# AudioMega_v1.net
KiCad netlist of a schematic drawn in EAGLE
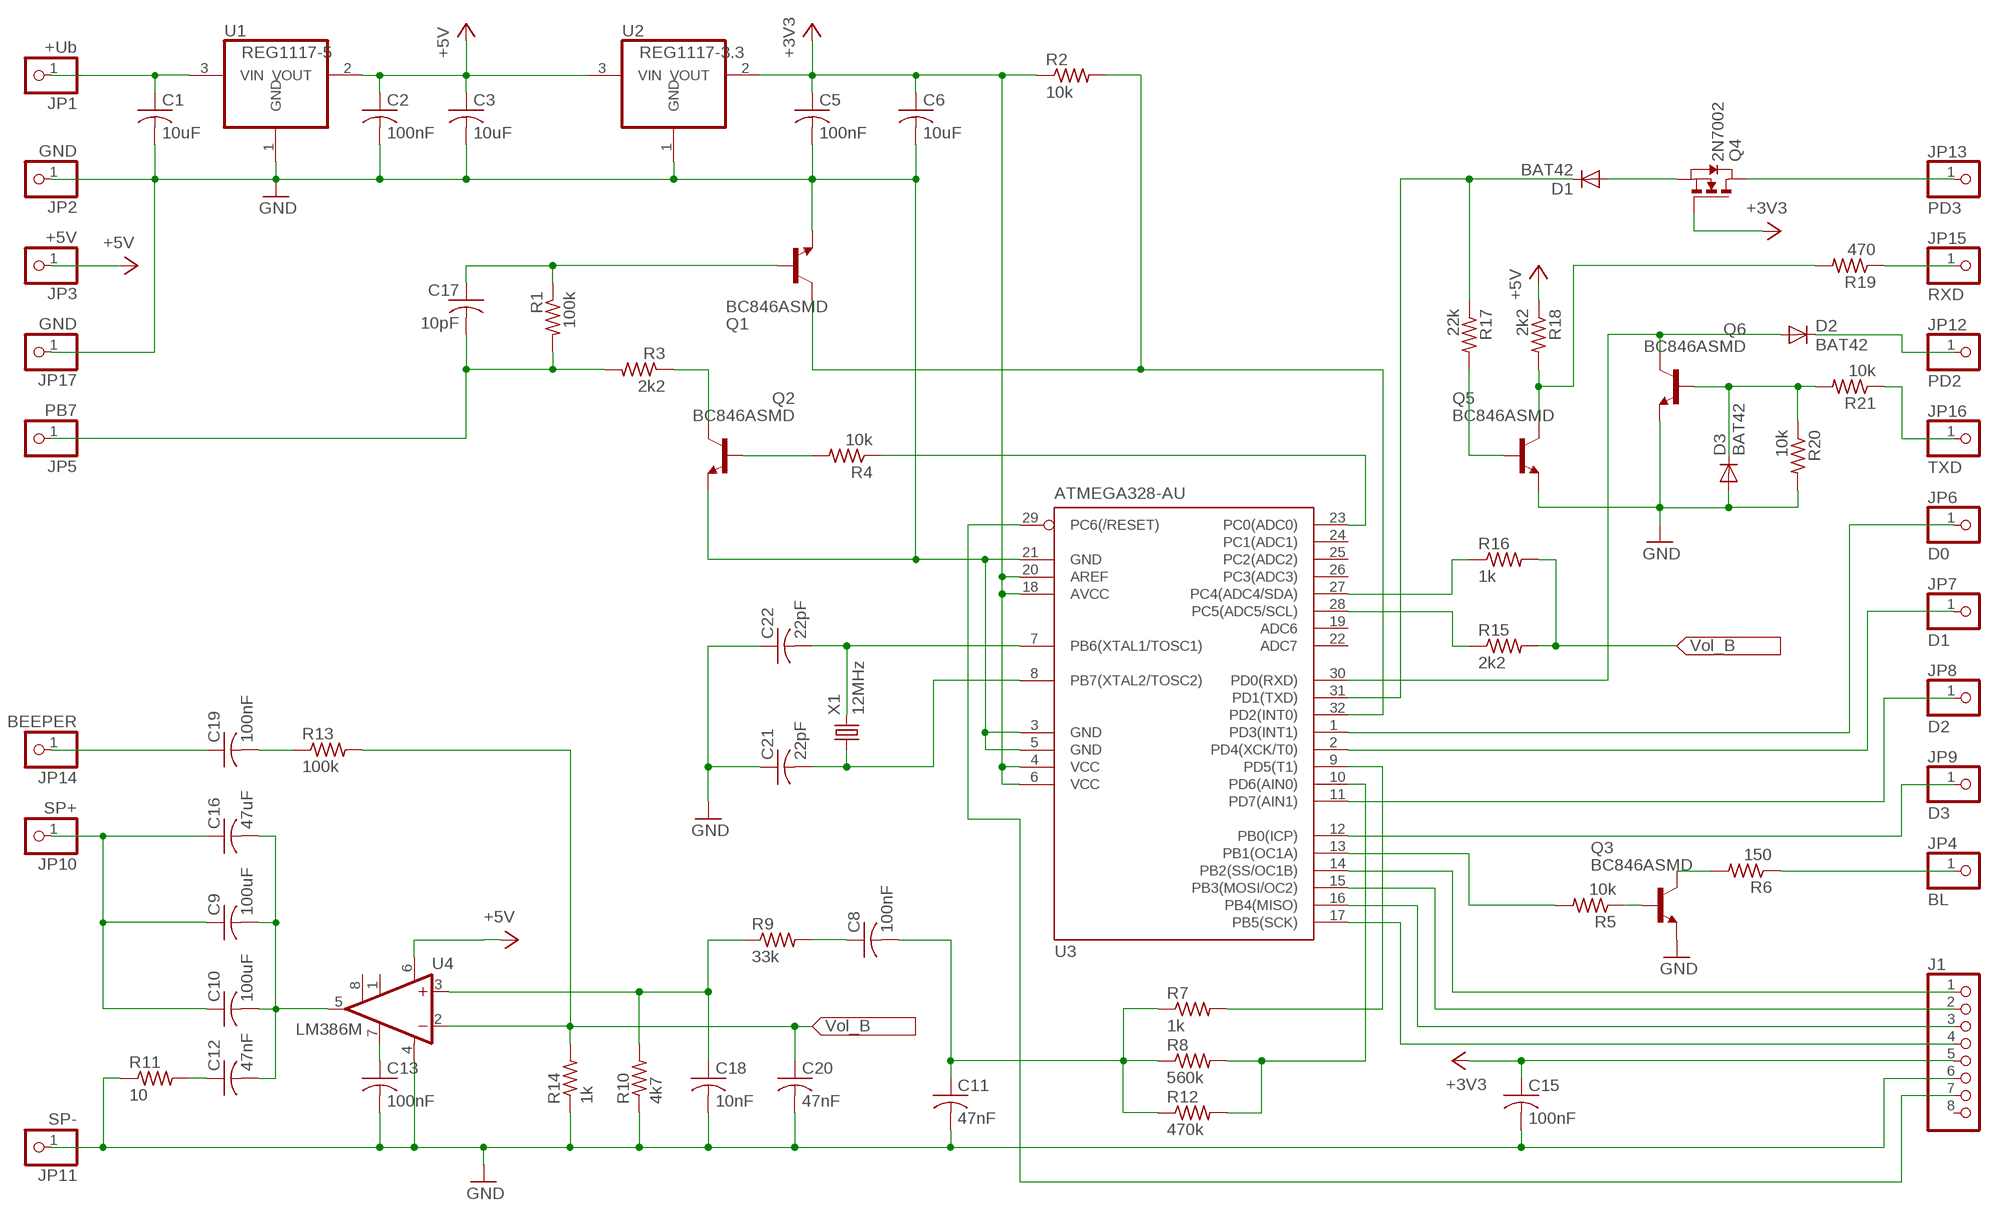
[diagram p0: schematic, sheet 1]

(export (version "E")
  (design (tool "Eeschema 10.0.6"))
  (components
    (comp (ref "C1")
      (value "10uF")
      (footprint "eagle-import:C1206")
      (libsource (lib "eagle-import") (part "C-USC1206"))
    )
    (comp (ref "C2")
      (value "100nF")
      (footprint "eagle-import:C1206")
      (libsource (lib "eagle-import") (part "C-USC1206"))
    )
    (comp (ref "C3")
      (value "10uF")
      (footprint "eagle-import:C1206")
      (libsource (lib "eagle-import") (part "C-USC1206"))
    )
    (comp (ref "C5")
      (value "100nF")
      (footprint "eagle-import:C1206")
      (libsource (lib "eagle-import") (part "C-USC1206"))
    )
    (comp (ref "C6")
      (value "10uF")
      (footprint "eagle-import:C1206")
      (libsource (lib "eagle-import") (part "C-USC1206"))
    )
    (comp (ref "C8")
      (value "100nF")
      (footprint "eagle-import:C1206")
      (libsource (lib "eagle-import") (part "C-USC1206"))
    )
    (comp (ref "C9")
      (value "100uF")
      (footprint "eagle-import:C1206")
      (libsource (lib "eagle-import") (part "C-USC1206"))
    )
    (comp (ref "C10")
      (value "100uF")
      (footprint "eagle-import:C1206")
      (libsource (lib "eagle-import") (part "C-USC1206"))
    )
    (comp (ref "C11")
      (value "47nF")
      (footprint "eagle-import:C1206")
      (libsource (lib "eagle-import") (part "C-USC1206"))
    )
    (comp (ref "C12")
      (value "47nF")
      (footprint "eagle-import:C1206")
      (libsource (lib "eagle-import") (part "C-USC1206"))
    )
    (comp (ref "C13")
      (value "100nF")
      (footprint "eagle-import:C1206")
      (libsource (lib "eagle-import") (part "C-USC1206"))
    )
    (comp (ref "C15")
      (value "100nF")
      (footprint "eagle-import:C1206")
      (libsource (lib "eagle-import") (part "C-USC1206"))
    )
    (comp (ref "C16")
      (value "47uF")
      (footprint "eagle-import:C1206")
      (libsource (lib "eagle-import") (part "C-USC1206"))
    )
    (comp (ref "C17")
      (value "10pF")
      (footprint "eagle-import:C1206")
      (libsource (lib "eagle-import") (part "C-USC1206"))
    )
    (comp (ref "C18")
      (value "10nF")
      (footprint "eagle-import:C1206")
      (libsource (lib "eagle-import") (part "C-USC1206"))
    )
    (comp (ref "C19")
      (value "100nF")
      (footprint "eagle-import:C1206")
      (libsource (lib "eagle-import") (part "C-USC1206"))
    )
    (comp (ref "C20")
      (value "47nF")
      (footprint "eagle-import:C1206")
      (libsource (lib "eagle-import") (part "C-USC1206"))
    )
    (comp (ref "C21")
      (value "22pF")
      (footprint "eagle-import:C1206")
      (libsource (lib "eagle-import") (part "C-USC1206"))
    )
    (comp (ref "C22")
      (value "22pF")
      (footprint "eagle-import:C1206")
      (libsource (lib "eagle-import") (part "C-USC1206"))
    )
    (comp (ref "D1")
      (value "BAT42")
      (footprint "eagle-import:SOD123")
      (libsource (lib "eagle-import") (part "DIODE-SOD123"))
    )
    (comp (ref "D2")
      (value "BAT42")
      (footprint "eagle-import:SOD123")
      (libsource (lib "eagle-import") (part "DIODE-SOD123"))
    )
    (comp (ref "D3")
      (value "BAT42")
      (footprint "eagle-import:SOD123")
      (libsource (lib "eagle-import") (part "DIODE-SOD123"))
    )
    (comp (ref "J1")
      (value "PINHD-1X8")
      (footprint "eagle-import:1X08")
      (libsource (lib "eagle-import") (part "PINHD-1X8"))
    )
    (comp (ref "JP1")
      (value "+Ub")
      (footprint "eagle-import:1X01")
      (libsource (lib "eagle-import") (part "PINHD-1X1"))
    )
    (comp (ref "JP2")
      (value "GND")
      (footprint "eagle-import:1X01")
      (libsource (lib "eagle-import") (part "PINHD-1X1"))
    )
    (comp (ref "JP3")
      (value "+5V")
      (footprint "eagle-import:1X01")
      (libsource (lib "eagle-import") (part "PINHD-1X1"))
    )
    (comp (ref "JP4")
      (value "BL")
      (footprint "eagle-import:1X01")
      (libsource (lib "eagle-import") (part "PINHD-1X1"))
    )
    (comp (ref "JP5")
      (value "PB7")
      (footprint "eagle-import:1X01")
      (libsource (lib "eagle-import") (part "PINHD-1X1"))
    )
    (comp (ref "JP6")
      (value "D0")
      (footprint "eagle-import:1X01")
      (libsource (lib "eagle-import") (part "PINHD-1X1"))
    )
    (comp (ref "JP7")
      (value "D1")
      (footprint "eagle-import:1X01")
      (libsource (lib "eagle-import") (part "PINHD-1X1"))
    )
    (comp (ref "JP8")
      (value "D2")
      (footprint "eagle-import:1X01")
      (libsource (lib "eagle-import") (part "PINHD-1X1"))
    )
    (comp (ref "JP9")
      (value "D3")
      (footprint "eagle-import:1X01")
      (libsource (lib "eagle-import") (part "PINHD-1X1"))
    )
    (comp (ref "JP10")
      (value "SP+")
      (footprint "eagle-import:1X01")
      (libsource (lib "eagle-import") (part "PINHD-1X1"))
    )
    (comp (ref "JP11")
      (value "SP-")
      (footprint "eagle-import:1X01")
      (libsource (lib "eagle-import") (part "PINHD-1X1"))
    )
    (comp (ref "JP12")
      (value "PD2")
      (footprint "eagle-import:1X01")
      (libsource (lib "eagle-import") (part "PINHD-1X1"))
    )
    (comp (ref "JP13")
      (value "PD3")
      (footprint "eagle-import:1X01")
      (libsource (lib "eagle-import") (part "PINHD-1X1"))
    )
    (comp (ref "JP14")
      (value "BEEPER")
      (footprint "eagle-import:1X01")
      (libsource (lib "eagle-import") (part "PINHD-1X1"))
    )
    (comp (ref "JP15")
      (value "RXD")
      (footprint "eagle-import:1X01")
      (libsource (lib "eagle-import") (part "PINHD-1X1"))
    )
    (comp (ref "JP16")
      (value "TXD")
      (footprint "eagle-import:1X01")
      (libsource (lib "eagle-import") (part "PINHD-1X1"))
    )
    (comp (ref "JP17")
      (value "GND")
      (footprint "eagle-import:1X01")
      (libsource (lib "eagle-import") (part "PINHD-1X1"))
    )
    (comp (ref "Q1")
      (value "BC846ASMD")
      (footprint "eagle-import:SOT23")
      (libsource (lib "eagle-import") (part "BC846SMDA"))
    )
    (comp (ref "Q2")
      (value "BC846ASMD")
      (footprint "eagle-import:SOT23")
      (libsource (lib "eagle-import") (part "BC846SMDA"))
    )
    (comp (ref "Q3")
      (value "BC846ASMD")
      (footprint "eagle-import:SOT23")
      (libsource (lib "eagle-import") (part "BC846SMDA"))
    )
    (comp (ref "Q4")
      (value "2N7002")
      (footprint "eagle-import:SOT-23")
      (libsource (lib "eagle-import") (part "NMOSSOT23"))
    )
    (comp (ref "Q5")
      (value "BC846ASMD")
      (footprint "eagle-import:SOT23")
      (libsource (lib "eagle-import") (part "BC846SMDA"))
    )
    (comp (ref "Q6")
      (value "BC846ASMD")
      (footprint "eagle-import:SOT23")
      (libsource (lib "eagle-import") (part "BC846SMDA"))
    )
    (comp (ref "R1")
      (value "100k")
      (footprint "eagle-import:R1206")
      (libsource (lib "eagle-import") (part "R-US_R1206"))
    )
    (comp (ref "R2")
      (value "10k")
      (footprint "eagle-import:R1206")
      (libsource (lib "eagle-import") (part "R-US_R1206"))
    )
    (comp (ref "R3")
      (value "2k2")
      (footprint "eagle-import:R1206")
      (libsource (lib "eagle-import") (part "R-US_R1206"))
    )
    (comp (ref "R4")
      (value "10k")
      (footprint "eagle-import:R1206")
      (libsource (lib "eagle-import") (part "R-US_R1206"))
    )
    (comp (ref "R5")
      (value "10k")
      (footprint "eagle-import:R1206")
      (libsource (lib "eagle-import") (part "R-US_R1206"))
    )
    (comp (ref "R6")
      (value "150")
      (footprint "eagle-import:R1206")
      (libsource (lib "eagle-import") (part "R-US_R1206"))
    )
    (comp (ref "R7")
      (value "1k")
      (footprint "eagle-import:R1206")
      (libsource (lib "eagle-import") (part "R-US_R1206"))
    )
    (comp (ref "R8")
      (value "560k")
      (footprint "eagle-import:R1206")
      (libsource (lib "eagle-import") (part "R-US_R1206"))
    )
    (comp (ref "R9")
      (value "33k")
      (footprint "eagle-import:R1206")
      (libsource (lib "eagle-import") (part "R-US_R1206"))
    )
    (comp (ref "R10")
      (value "4k7")
      (footprint "eagle-import:R1206")
      (libsource (lib "eagle-import") (part "R-US_R1206"))
    )
    (comp (ref "R11")
      (value "10")
      (footprint "eagle-import:R1206")
      (libsource (lib "eagle-import") (part "R-US_R1206"))
    )
    (comp (ref "R12")
      (value "470k")
      (footprint "eagle-import:R1206")
      (libsource (lib "eagle-import") (part "R-US_R1206"))
    )
    (comp (ref "R13")
      (value "100k")
      (footprint "eagle-import:R1206")
      (libsource (lib "eagle-import") (part "R-US_R1206"))
    )
    (comp (ref "R14")
      (value "1k")
      (footprint "eagle-import:R1206")
      (libsource (lib "eagle-import") (part "R-US_R1206"))
    )
    (comp (ref "R15")
      (value "2k2")
      (footprint "eagle-import:R1206")
      (libsource (lib "eagle-import") (part "R-US_R1206"))
    )
    (comp (ref "R16")
      (value "1k")
      (footprint "eagle-import:R1206")
      (libsource (lib "eagle-import") (part "R-US_R1206"))
    )
    (comp (ref "R17")
      (value "22k")
      (footprint "eagle-import:R1206")
      (libsource (lib "eagle-import") (part "R-US_R1206"))
    )
    (comp (ref "R18")
      (value "2k2")
      (footprint "eagle-import:R1206")
      (libsource (lib "eagle-import") (part "R-US_R1206"))
    )
    (comp (ref "R19")
      (value "470")
      (footprint "eagle-import:R1206")
      (libsource (lib "eagle-import") (part "R-US_R1206"))
    )
    (comp (ref "R20")
      (value "10k")
      (footprint "eagle-import:R1206")
      (libsource (lib "eagle-import") (part "R-US_R1206"))
    )
    (comp (ref "R21")
      (value "10k")
      (footprint "eagle-import:R1206")
      (libsource (lib "eagle-import") (part "R-US_R1206"))
    )
    (comp (ref "U1")
      (value "REG1117-5")
      (footprint "eagle-import:SOT223")
      (fields (field (name "MPN") "REG1117"))
      (libsource (lib "eagle-import") (part "REG1117"))
    )
    (comp (ref "U2")
      (value "REG1117-3.3")
      (footprint "eagle-import:SOT223")
      (fields (field (name "MPN") "REG1117"))
      (libsource (lib "eagle-import") (part "REG1117"))
    )
    (comp (ref "U3")
      (value "ATMEGA328-AU")
      (footprint "eagle-import:TQFP32-08")
      (fields (field (name "MPN") "ATMEGA8-16AU"))
      (libsource (lib "eagle-import") (part "MEGA8-AI"))
    )
    (comp (ref "U4")
      (value "LM386M")
      (footprint "eagle-import:SO08")
      (libsource (lib "eagle-import") (part "LM386?-M1"))
    )
    (comp (ref "X1")
      (value "12MHz")
      (footprint "eagle-import:HC49UP")
      (libsource (lib "eagle-import") (part "CRYSTALHC49UP"))
    )
  )
  (nets
    (net (code "1") (name "+3V3") (class "Default")
      (node (ref "C15") (pin "1") (pinfunction "1_1") (pintype "passive"))
      (node (ref "C5") (pin "1") (pinfunction "1_1") (pintype "passive"))
      (node (ref "C6") (pin "1") (pinfunction "1_1") (pintype "passive"))
      (node (ref "J1") (pin "5") (pinfunction "5_5") (pintype "passive"))
      (node (ref "Q4") (pin "3") (pinfunction "G_3") (pintype "passive"))
      (node (ref "R2") (pin "1") (pinfunction "1_1") (pintype "passive"))
      (node (ref "U2") (pin "2") (pinfunction "VOUT_2") (pintype "output"))
      (node (ref "U3") (pin "18") (pinfunction "AVCC_18") (pintype "power_in"))
      (node (ref "U3") (pin "20") (pinfunction "AREF_20") (pintype "passive"))
      (node (ref "U3") (pin "4") (pinfunction "VCC_4") (pintype "power_in"))
      (node (ref "U3") (pin "6") (pinfunction "VCC_6") (pintype "power_in"))
    )
    (net (code "2") (name "+5V") (class "Default")
      (node (ref "C2") (pin "1") (pinfunction "1_1") (pintype "passive"))
      (node (ref "C3") (pin "1") (pinfunction "1_1") (pintype "passive"))
      (node (ref "JP3") (pin "1") (pinfunction "1_1") (pintype "passive"))
      (node (ref "R18") (pin "1") (pinfunction "1_1") (pintype "passive"))
      (node (ref "U1") (pin "2") (pinfunction "VOUT_2") (pintype "output"))
      (node (ref "U2") (pin "3") (pinfunction "VIN_3") (pintype "input"))
      (node (ref "U4") (pin "6") (pinfunction "VS_6") (pintype "power_in"))
    )
    (net (code "3") (name "/VOL_B") (class "Default")
      (node (ref "C20") (pin "1") (pinfunction "1_1") (pintype "passive"))
      (node (ref "R13") (pin "2") (pinfunction "2_2") (pintype "passive"))
      (node (ref "R14") (pin "2") (pinfunction "2_2") (pintype "passive"))
      (node (ref "R15") (pin "2") (pinfunction "2_2") (pintype "passive"))
      (node (ref "R16") (pin "2") (pinfunction "2_2") (pintype "passive"))
      (node (ref "U4") (pin "2") (pinfunction "-IN_2") (pintype "input"))
    )
    (net (code "4") (name "GND") (class "Default")
      (node (ref "C1") (pin "2") (pinfunction "2_2") (pintype "passive"))
      (node (ref "C11") (pin "2") (pinfunction "2_2") (pintype "passive"))
      (node (ref "C13") (pin "2") (pinfunction "2_2") (pintype "passive"))
      (node (ref "C15") (pin "2") (pinfunction "2_2") (pintype "passive"))
      (node (ref "C18") (pin "2") (pinfunction "2_2") (pintype "passive"))
      (node (ref "C2") (pin "2") (pinfunction "2_2") (pintype "passive"))
      (node (ref "C20") (pin "2") (pinfunction "2_2") (pintype "passive"))
      (node (ref "C21") (pin "1") (pinfunction "1_1") (pintype "passive"))
      (node (ref "C22") (pin "1") (pinfunction "1_1") (pintype "passive"))
      (node (ref "C3") (pin "2") (pinfunction "2_2") (pintype "passive"))
      (node (ref "C5") (pin "2") (pinfunction "2_2") (pintype "passive"))
      (node (ref "C6") (pin "2") (pinfunction "2_2") (pintype "passive"))
      (node (ref "D3") (pin "A") (pinfunction "A_A") (pintype "passive"))
      (node (ref "J1") (pin "6") (pinfunction "6_6") (pintype "passive"))
      (node (ref "JP11") (pin "1") (pinfunction "1_1") (pintype "passive"))
      (node (ref "JP17") (pin "1") (pinfunction "1_1") (pintype "passive"))
      (node (ref "JP2") (pin "1") (pinfunction "1_1") (pintype "passive"))
      (node (ref "Q1") (pin "2") (pinfunction "E_2") (pintype "passive"))
      (node (ref "Q2") (pin "2") (pinfunction "E_2") (pintype "passive"))
      (node (ref "Q3") (pin "2") (pinfunction "E_2") (pintype "passive"))
      (node (ref "Q5") (pin "2") (pinfunction "E_2") (pintype "passive"))
      (node (ref "Q6") (pin "2") (pinfunction "E_2") (pintype "passive"))
      (node (ref "R10") (pin "1") (pinfunction "1_1") (pintype "passive"))
      (node (ref "R11") (pin "1") (pinfunction "1_1") (pintype "passive"))
      (node (ref "R14") (pin "1") (pinfunction "1_1") (pintype "passive"))
      (node (ref "R20") (pin "2") (pinfunction "2_2") (pintype "passive"))
      (node (ref "U1") (pin "1") (pinfunction "GND_1") (pintype "power_in"))
      (node (ref "U2") (pin "1") (pinfunction "GND_1") (pintype "power_in"))
      (node (ref "U3") (pin "21") (pinfunction "GND_21") (pintype "power_in"))
      (node (ref "U3") (pin "3") (pinfunction "GND_3") (pintype "power_in"))
      (node (ref "U3") (pin "5") (pinfunction "GND_5") (pintype "power_in"))
      (node (ref "U4") (pin "4") (pinfunction "GND_4") (pintype "power_in"))
    )
    (net (code "5") (name "Net-(C8-Pad1)") (class "Default")
      (node (ref "C8") (pin "1") (pinfunction "1_1") (pintype "passive"))
      (node (ref "R9") (pin "2") (pinfunction "2_2") (pintype "passive"))
    )
    (net (code "6") (name "Net-(C10-Pad1)") (class "Default")
      (node (ref "C10") (pin "1") (pinfunction "1_1") (pintype "passive"))
      (node (ref "C16") (pin "1") (pinfunction "1_1") (pintype "passive"))
      (node (ref "C9") (pin "1") (pinfunction "1_1") (pintype "passive"))
      (node (ref "JP10") (pin "1") (pinfunction "1_1") (pintype "passive"))
    )
    (net (code "7") (name "Net-(C11-Pad1)") (class "Default")
      (node (ref "C11") (pin "1") (pinfunction "1_1") (pintype "passive"))
      (node (ref "C8") (pin "2") (pinfunction "2_2") (pintype "passive"))
      (node (ref "R12") (pin "1") (pinfunction "1_1") (pintype "passive"))
      (node (ref "R7") (pin "1") (pinfunction "1_1") (pintype "passive"))
      (node (ref "R8") (pin "1") (pinfunction "1_1") (pintype "passive"))
    )
    (net (code "8") (name "Net-(C12-Pad1)") (class "Default")
      (node (ref "C12") (pin "1") (pinfunction "1_1") (pintype "passive"))
      (node (ref "R11") (pin "2") (pinfunction "2_2") (pintype "passive"))
    )
    (net (code "9") (name "Net-(C17-Pad2)") (class "Default")
      (node (ref "C17") (pin "2") (pinfunction "2_2") (pintype "passive"))
      (node (ref "JP5") (pin "1") (pinfunction "1_1") (pintype "passive"))
      (node (ref "R1") (pin "2") (pinfunction "2_2") (pintype "passive"))
      (node (ref "R3") (pin "2") (pinfunction "2_2") (pintype "passive"))
    )
    (net (code "10") (name "Net-(C19-Pad1)") (class "Default")
      (node (ref "C19") (pin "1") (pinfunction "1_1") (pintype "passive"))
      (node (ref "JP14") (pin "1") (pinfunction "1_1") (pintype "passive"))
    )
    (net (code "11") (name "Net-(C19-Pad2)") (class "Default")
      (node (ref "C19") (pin "2") (pinfunction "2_2") (pintype "passive"))
      (node (ref "R13") (pin "1") (pinfunction "1_1") (pintype "passive"))
    )
    (net (code "12") (name "Net-(D2-PadC)") (class "Default")
      (node (ref "D2") (pin "C") (pinfunction "C_C") (pintype "passive"))
      (node (ref "JP12") (pin "1") (pinfunction "1_1") (pintype "passive"))
    )
    (net (code "13") (name "Net-(JP4-Pad1)") (class "Default")
      (node (ref "JP4") (pin "1") (pinfunction "1_1") (pintype "passive"))
      (node (ref "R6") (pin "1") (pinfunction "1_1") (pintype "passive"))
    )
    (net (code "14") (name "Net-(JP15-Pad1)") (class "Default")
      (node (ref "JP15") (pin "1") (pinfunction "1_1") (pintype "passive"))
      (node (ref "R19") (pin "1") (pinfunction "1_1") (pintype "passive"))
    )
    (net (code "15") (name "Net-(JP16-Pad1)") (class "Default")
      (node (ref "JP16") (pin "1") (pinfunction "1_1") (pintype "passive"))
      (node (ref "R21") (pin "1") (pinfunction "1_1") (pintype "passive"))
    )
    (net (code "16") (name "Net-(Q1-B)") (class "Default")
      (node (ref "C17") (pin "1") (pinfunction "1_1") (pintype "passive"))
      (node (ref "Q1") (pin "1") (pinfunction "B_1") (pintype "passive"))
      (node (ref "R1") (pin "1") (pinfunction "1_1") (pintype "passive"))
    )
    (net (code "17") (name "Net-(Q1-C)") (class "Default")
      (node (ref "Q1") (pin "3") (pinfunction "C_3") (pintype "passive"))
      (node (ref "R2") (pin "2") (pinfunction "2_2") (pintype "passive"))
      (node (ref "U3") (pin "32") (pinfunction "PD2(INT0)_32") (pintype "bidirectional"))
    )
    (net (code "18") (name "Net-(Q2-B)") (class "Default")
      (node (ref "Q2") (pin "1") (pinfunction "B_1") (pintype "passive"))
      (node (ref "R4") (pin "2") (pinfunction "2_2") (pintype "passive"))
    )
    (net (code "19") (name "Net-(Q2-C)") (class "Default")
      (node (ref "Q2") (pin "3") (pinfunction "C_3") (pintype "passive"))
      (node (ref "R3") (pin "1") (pinfunction "1_1") (pintype "passive"))
    )
    (net (code "20") (name "Net-(Q3-B)") (class "Default")
      (node (ref "Q3") (pin "1") (pinfunction "B_1") (pintype "passive"))
      (node (ref "R5") (pin "1") (pinfunction "1_1") (pintype "passive"))
    )
    (net (code "21") (name "Net-(Q3-C)") (class "Default")
      (node (ref "Q3") (pin "3") (pinfunction "C_3") (pintype "passive"))
      (node (ref "R6") (pin "2") (pinfunction "2_2") (pintype "passive"))
    )
    (net (code "22") (name "Net-(Q4-D)") (class "Default")
      (node (ref "JP13") (pin "1") (pinfunction "1_1") (pintype "passive"))
      (node (ref "Q4") (pin "1") (pinfunction "D_1") (pintype "passive"))
    )
    (net (code "23") (name "Net-(Q4-S)") (class "Default")
      (node (ref "D1") (pin "A") (pinfunction "A_A") (pintype "passive"))
      (node (ref "Q4") (pin "2") (pinfunction "S_2") (pintype "passive"))
    )
    (net (code "24") (name "Net-(Q5-B)") (class "Default")
      (node (ref "Q5") (pin "1") (pinfunction "B_1") (pintype "passive"))
      (node (ref "R17") (pin "2") (pinfunction "2_2") (pintype "passive"))
    )
    (net (code "25") (name "Net-(Q5-C)") (class "Default")
      (node (ref "Q5") (pin "3") (pinfunction "C_3") (pintype "passive"))
      (node (ref "R18") (pin "2") (pinfunction "2_2") (pintype "passive"))
      (node (ref "R19") (pin "2") (pinfunction "2_2") (pintype "passive"))
    )
    (net (code "26") (name "Net-(Q6-B)") (class "Default")
      (node (ref "D3") (pin "C") (pinfunction "C_C") (pintype "passive"))
      (node (ref "Q6") (pin "1") (pinfunction "B_1") (pintype "passive"))
      (node (ref "R20") (pin "1") (pinfunction "1_1") (pintype "passive"))
      (node (ref "R21") (pin "2") (pinfunction "2_2") (pintype "passive"))
    )
    (net (code "27") (name "Net-(Q6-C)") (class "Default")
      (node (ref "D2") (pin "A") (pinfunction "A_A") (pintype "passive"))
      (node (ref "Q6") (pin "3") (pinfunction "C_3") (pintype "passive"))
      (node (ref "U3") (pin "30") (pinfunction "PD0(RXD)_30") (pintype "bidirectional"))
    )
    (net (code "28") (name "Net-(U1-VIN)") (class "Default")
      (node (ref "C1") (pin "1") (pinfunction "1_1") (pintype "passive"))
      (node (ref "JP1") (pin "1") (pinfunction "1_1") (pintype "passive"))
      (node (ref "U1") (pin "3") (pinfunction "VIN_3") (pintype "input"))
    )
    (net (code "29") (name "Net-(U3-PB0(ICP))") (class "Default")
      (node (ref "JP9") (pin "1") (pinfunction "1_1") (pintype "passive"))
      (node (ref "U3") (pin "12") (pinfunction "PB0(ICP)_12") (pintype "bidirectional"))
    )
    (net (code "30") (name "Net-(U3-PB1(OC1A))") (class "Default")
      (node (ref "R5") (pin "2") (pinfunction "2_2") (pintype "passive"))
      (node (ref "U3") (pin "13") (pinfunction "PB1(OC1A)_13") (pintype "bidirectional"))
    )
    (net (code "31") (name "Net-(U3-PB2(SS{slash}OC1B))") (class "Default")
      (node (ref "J1") (pin "1") (pinfunction "1_1") (pintype "passive"))
      (node (ref "U3") (pin "14") (pinfunction "PB2(SS/OC1B)_14") (pintype "bidirectional"))
    )
    (net (code "32") (name "Net-(U3-PB3(MOSI{slash}OC2))") (class "Default")
      (node (ref "J1") (pin "2") (pinfunction "2_2") (pintype "passive"))
      (node (ref "U3") (pin "15") (pinfunction "PB3(MOSI/OC2)_15") (pintype "bidirectional"))
    )
    (net (code "33") (name "Net-(U3-PB4(MISO))") (class "Default")
      (node (ref "J1") (pin "3") (pinfunction "3_3") (pintype "passive"))
      (node (ref "U3") (pin "16") (pinfunction "PB4(MISO)_16") (pintype "bidirectional"))
    )
    (net (code "34") (name "Net-(U3-PB5(SCK))") (class "Default")
      (node (ref "J1") (pin "4") (pinfunction "4_4") (pintype "passive"))
      (node (ref "U3") (pin "17") (pinfunction "PB5(SCK)_17") (pintype "bidirectional"))
    )
    (net (code "35") (name "Net-(U3-PB6(XTAL1{slash}TOSC1))") (class "Default")
      (node (ref "C22") (pin "2") (pinfunction "2_2") (pintype "passive"))
      (node (ref "U3") (pin "7") (pinfunction "PB6(XTAL1/TOSC1)_7") (pintype "bidirectional"))
      (node (ref "X1") (pin "2") (pinfunction "2_2") (pintype "passive"))
    )
    (net (code "36") (name "Net-(U3-PB7(XTAL2{slash}TOSC2))") (class "Default")
      (node (ref "C21") (pin "2") (pinfunction "2_2") (pintype "passive"))
      (node (ref "U3") (pin "8") (pinfunction "PB7(XTAL2/TOSC2)_8") (pintype "bidirectional"))
      (node (ref "X1") (pin "1") (pinfunction "1_1") (pintype "passive"))
    )
    (net (code "37") (name "Net-(U3-PC0(ADC0))") (class "Default")
      (node (ref "R4") (pin "1") (pinfunction "1_1") (pintype "passive"))
      (node (ref "U3") (pin "23") (pinfunction "PC0(ADC0)_23") (pintype "bidirectional"))
    )
    (net (code "38") (name "Net-(U3-PC4(ADC4{slash}SDA))") (class "Default")
      (node (ref "R16") (pin "1") (pinfunction "1_1") (pintype "passive"))
      (node (ref "U3") (pin "27") (pinfunction "PC4(ADC4/SDA)_27") (pintype "bidirectional"))
    )
    (net (code "39") (name "Net-(U3-PC5(ADC5{slash}SCL))") (class "Default")
      (node (ref "R15") (pin "1") (pinfunction "1_1") (pintype "passive"))
      (node (ref "U3") (pin "28") (pinfunction "PC5(ADC5/SCL)_28") (pintype "bidirectional"))
    )
    (net (code "40") (name "Net-(U3-PC6({slash}RESET))") (class "Default")
      (node (ref "J1") (pin "7") (pinfunction "7_7") (pintype "passive"))
      (node (ref "U3") (pin "29") (pinfunction "PC6(/RESET)_29") (pintype "bidirectional"))
    )
    (net (code "41") (name "Net-(U3-PD1(TXD))") (class "Default")
      (node (ref "D1") (pin "C") (pinfunction "C_C") (pintype "passive"))
      (node (ref "R17") (pin "1") (pinfunction "1_1") (pintype "passive"))
      (node (ref "U3") (pin "31") (pinfunction "PD1(TXD)_31") (pintype "bidirectional"))
    )
    (net (code "42") (name "Net-(U3-PD3(INT1))") (class "Default")
      (node (ref "JP6") (pin "1") (pinfunction "1_1") (pintype "passive"))
      (node (ref "U3") (pin "1") (pinfunction "PD3(INT1)_1") (pintype "bidirectional"))
    )
    (net (code "43") (name "Net-(U3-PD4(XCK{slash}T0))") (class "Default")
      (node (ref "JP7") (pin "1") (pinfunction "1_1") (pintype "passive"))
      (node (ref "U3") (pin "2") (pinfunction "PD4(XCK/T0)_2") (pintype "bidirectional"))
    )
    (net (code "44") (name "Net-(U3-PD5(T1))") (class "Default")
      (node (ref "R7") (pin "2") (pinfunction "2_2") (pintype "passive"))
      (node (ref "U3") (pin "9") (pinfunction "PD5(T1)_9") (pintype "bidirectional"))
    )
    (net (code "45") (name "Net-(U3-PD6(AIN0))") (class "Default")
      (node (ref "R12") (pin "2") (pinfunction "2_2") (pintype "passive"))
      (node (ref "R8") (pin "2") (pinfunction "2_2") (pintype "passive"))
      (node (ref "U3") (pin "10") (pinfunction "PD6(AIN0)_10") (pintype "bidirectional"))
    )
    (net (code "46") (name "Net-(U3-PD7(AIN1))") (class "Default")
      (node (ref "JP8") (pin "1") (pinfunction "1_1") (pintype "passive"))
      (node (ref "U3") (pin "11") (pinfunction "PD7(AIN1)_11") (pintype "bidirectional"))
    )
    (net (code "47") (name "Net-(U4-+IN)") (class "Default")
      (node (ref "C18") (pin "1") (pinfunction "1_1") (pintype "passive"))
      (node (ref "R10") (pin "2") (pinfunction "2_2") (pintype "passive"))
      (node (ref "R9") (pin "1") (pinfunction "1_1") (pintype "passive"))
      (node (ref "U4") (pin "3") (pinfunction "+IN_3") (pintype "input"))
    )
    (net (code "48") (name "Net-(U4-BYPASS)") (class "Default")
      (node (ref "C13") (pin "1") (pinfunction "1_1") (pintype "passive"))
      (node (ref "U4") (pin "7") (pinfunction "BYPASS_7") (pintype "passive"))
    )
    (net (code "49") (name "Net-(U4-OUT)") (class "Default")
      (node (ref "C10") (pin "2") (pinfunction "2_2") (pintype "passive"))
      (node (ref "C12") (pin "2") (pinfunction "2_2") (pintype "passive"))
      (node (ref "C16") (pin "2") (pinfunction "2_2") (pintype "passive"))
      (node (ref "C9") (pin "2") (pinfunction "2_2") (pintype "passive"))
      (node (ref "U4") (pin "5") (pinfunction "OUT_5") (pintype "output"))
    )
    (net (code "50") (name "unconnected-(J1-Pad8)") (class "Default")
      (node (ref "J1") (pin "8") (pinfunction "8_8") (pintype "passive"))
    )
    (net (code "51") (name "unconnected-(U3-ADC6-Pad19)") (class "Default")
      (node (ref "U3") (pin "19") (pinfunction "ADC6_19") (pintype "bidirectional"))
    )
    (net (code "52") (name "unconnected-(U3-ADC7-Pad22)") (class "Default")
      (node (ref "U3") (pin "22") (pinfunction "ADC7_22") (pintype "bidirectional"))
    )
    (net (code "53") (name "unconnected-(U3-PC1(ADC1)-Pad24)") (class "Default")
      (node (ref "U3") (pin "24") (pinfunction "PC1(ADC1)_24") (pintype "bidirectional"))
    )
    (net (code "54") (name "unconnected-(U3-PC2(ADC2)-Pad25)") (class "Default")
      (node (ref "U3") (pin "25") (pinfunction "PC2(ADC2)_25") (pintype "bidirectional"))
    )
    (net (code "55") (name "unconnected-(U3-PC3(ADC3)-Pad26)") (class "Default")
      (node (ref "U3") (pin "26") (pinfunction "PC3(ADC3)_26") (pintype "bidirectional"))
    )
    (net (code "56") (name "unconnected-(U4-GAIN-Pad1)") (class "Default")
      (node (ref "U4") (pin "1") (pinfunction "GAIN_1") (pintype "passive"))
    )
    (net (code "57") (name "unconnected-(U4-GAIN-Pad8)") (class "Default")
      (node (ref "U4") (pin "8") (pinfunction "GAIN_8") (pintype "passive"))
    )
  )
)
